# SBDBT.net
KiCad netlist of a schematic drawn in EAGLE
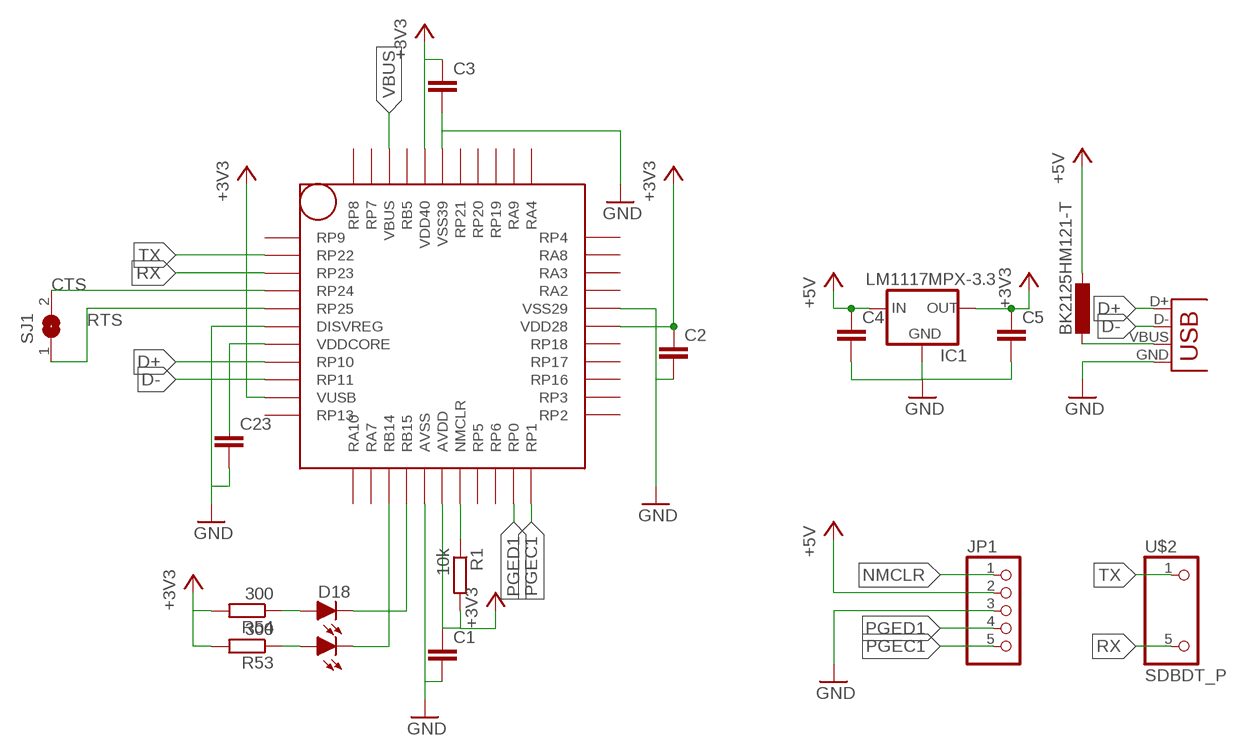
[diagram p0: schematic, sheet 1]

(export (version "E")
  (design (tool "Eeschema 10.0.6"))
  (components
    (comp (ref "BK2125HM121-T")
      (value "L-EUL2012C")
      (footprint "eagle-import:L2012C")
      (libsource (lib "eagle-import") (part "L-EUL2012C"))
    )
    (comp (ref "C1")
      (value "C-EUC0603K")
      (footprint "eagle-import:C0603K")
      (libsource (lib "eagle-import") (part "C-EUC0603K"))
    )
    (comp (ref "C2")
      (value "C-EUC0603K")
      (footprint "eagle-import:C0603K")
      (libsource (lib "eagle-import") (part "C-EUC0603K"))
    )
    (comp (ref "C3")
      (value "C-EUC0603K")
      (footprint "eagle-import:C0603K")
      (libsource (lib "eagle-import") (part "C-EUC0603K"))
    )
    (comp (ref "C4")
      (value "C-EUC0603K")
      (footprint "eagle-import:C0603K")
      (libsource (lib "eagle-import") (part "C-EUC0603K"))
    )
    (comp (ref "C5")
      (value "C-EUC0603K")
      (footprint "eagle-import:C0603K")
      (libsource (lib "eagle-import") (part "C-EUC0603K"))
    )
    (comp (ref "C23")
      (value "C-EUC0603K")
      (footprint "eagle-import:C0603K")
      (libsource (lib "eagle-import") (part "C-EUC0603K"))
    )
    (comp (ref "D18")
      (value "SEC2XX4")
      (footprint "eagle-import:LED3025")
      (libsource (lib "eagle-import") (part "SEC2XX4"))
    )
    (comp (ref "IC1")
      (value "LM1117MPX-3.3")
      (footprint "eagle-import:SOT223")
      (libsource (lib "eagle-import") (part "LM1117"))
    )
    (comp (ref "JP1")
      (value "PINHD-1X5")
      (footprint "eagle-import:1X05")
      (libsource (lib "eagle-import") (part "PINHD-1X5"))
    )
    (comp (ref "R1")
      (value "10k")
      (footprint "eagle-import:R0603")
      (libsource (lib "eagle-import") (part "R-EU_R0603"))
    )
    (comp (ref "R53")
      (value "300")
      (footprint "eagle-import:R0603")
      (libsource (lib "eagle-import") (part "R-EU_R0603"))
    )
    (comp (ref "R54")
      (value "300")
      (footprint "eagle-import:R0603")
      (libsource (lib "eagle-import") (part "R-EU_R0603"))
    )
    (comp (ref "SJ1") (value "SJ") (footprint "eagle-import:SJ") (libsource (lib "eagle-import") (part "SJ")))
    (comp (ref "U$1")
      (value "PIC24FJ64GB004")
      (footprint "eagle-import:SQFP-S-10X10-44")
      (libsource (lib "eagle-import") (part "PIC24FJ64GB004"))
    )
    (comp (ref "U$2")
      (value "SDBDT_P")
      (footprint "eagle-import:SDBDT_P")
      (libsource (lib "eagle-import") (part "SDBDT_P"))
    )
    (comp (ref "X2")
      (value "USB_")
      (footprint "eagle-import:USB-A-S-SILK-FEMALE")
      (libsource (lib "eagle-import") (part "USB_"))
    )
  )
  (nets
    (net (code "1") (name "+3V3") (class "Default")
      (node (ref "C1") (pin "1") (pinfunction "1_1") (pintype "passive"))
      (node (ref "C2") (pin "1") (pinfunction "1_1") (pintype "passive"))
      (node (ref "C3") (pin "1") (pinfunction "1_1") (pintype "passive"))
      (node (ref "C5") (pin "1") (pinfunction "1_1") (pintype "passive"))
      (node (ref "IC1") (pin "2") (pinfunction "OUT1_2") (pintype "passive"))
      (node (ref "IC1") (pin "4") (pinfunction "OUT_4") (pintype "passive"))
      (node (ref "R1") (pin "2") (pinfunction "2_2") (pintype "passive"))
      (node (ref "R53") (pin "2") (pinfunction "2_2") (pintype "passive"))
      (node (ref "R54") (pin "2") (pinfunction "2_2") (pintype "passive"))
      (node (ref "U$1") (pin "AVDD") (pinfunction "AVDD_AVDD") (pintype "bidirectional"))
      (node (ref "U$1") (pin "VDD28") (pinfunction "VDD28_VDD28") (pintype "bidirectional"))
      (node (ref "U$1") (pin "VDD40") (pinfunction "VDD40_VDD40") (pintype "bidirectional"))
      (node (ref "U$1") (pin "VUSB") (pinfunction "VUSB_VUSB") (pintype "bidirectional"))
    )
    (net (code "2") (name "+5V") (class "Default")
      (node (ref "BK2125HM121-T") (pin "1") (pinfunction "1_1") (pintype "passive"))
      (node (ref "C4") (pin "1") (pinfunction "1_1") (pintype "passive"))
      (node (ref "IC1") (pin "3") (pinfunction "IN_3") (pintype "input"))
      (node (ref "JP1") (pin "2") (pinfunction "2_2") (pintype "passive"))
    )
    (net (code "3") (name "/CTS") (class "Default")
      (node (ref "SJ1") (pin "2") (pinfunction "2_2") (pintype "passive"))
      (node (ref "U$1") (pin "RP24") (pinfunction "RP24_RP24") (pintype "bidirectional"))
    )
    (net (code "4") (name "/RTS") (class "Default")
      (node (ref "SJ1") (pin "1") (pinfunction "1_1") (pintype "passive"))
      (node (ref "U$1") (pin "RP25") (pinfunction "RP25_RP25") (pintype "bidirectional"))
    )
    (net (code "5") (name "D+") (class "Default")
      (node (ref "U$1") (pin "RP10") (pinfunction "RP10_RP10") (pintype "bidirectional"))
      (node (ref "X2") (pin "D+") (pinfunction "D+_D+") (pintype "bidirectional"))
    )
    (net (code "6") (name "D-") (class "Default")
      (node (ref "U$1") (pin "RP11") (pinfunction "RP11_RP11") (pintype "bidirectional"))
      (node (ref "X2") (pin "D-") (pinfunction "D-_D-") (pintype "bidirectional"))
    )
    (net (code "7") (name "GND") (class "Default")
      (node (ref "C1") (pin "2") (pinfunction "2_2") (pintype "passive"))
      (node (ref "C2") (pin "2") (pinfunction "2_2") (pintype "passive"))
      (node (ref "C23") (pin "2") (pinfunction "2_2") (pintype "passive"))
      (node (ref "C3") (pin "2") (pinfunction "2_2") (pintype "passive"))
      (node (ref "C4") (pin "2") (pinfunction "2_2") (pintype "passive"))
      (node (ref "C5") (pin "2") (pinfunction "2_2") (pintype "passive"))
      (node (ref "IC1") (pin "1") (pinfunction "GND_1") (pintype "input"))
      (node (ref "JP1") (pin "3") (pinfunction "3_3") (pintype "passive"))
      (node (ref "U$1") (pin "AVSS") (pinfunction "AVSS_AVSS") (pintype "bidirectional"))
      (node (ref "U$1") (pin "DISVREG") (pinfunction "DISVREG_DISVREG") (pintype "bidirectional"))
      (node (ref "U$1") (pin "VSS29") (pinfunction "VSS29_VSS29") (pintype "bidirectional"))
      (node (ref "U$1") (pin "VSS39") (pinfunction "VSS39_VSS39") (pintype "bidirectional"))
      (node (ref "X2") (pin "GND") (pinfunction "GND_GND") (pintype "bidirectional"))
    )
    (net (code "8") (name "NMCLR") (class "Default")
      (node (ref "JP1") (pin "1") (pinfunction "1_1") (pintype "passive"))
      (node (ref "R1") (pin "1") (pinfunction "1_1") (pintype "passive"))
      (node (ref "U$1") (pin "NMCLR") (pinfunction "NMCLR_NMCLR") (pintype "bidirectional"))
    )
    (net (code "9") (name "Net-(C23-Pad1)") (class "Default")
      (node (ref "C23") (pin "1") (pinfunction "1_1") (pintype "passive"))
      (node (ref "U$1") (pin "VDDCORE") (pinfunction "VDDCORE_VDDCORE") (pintype "bidirectional"))
    )
    (net (code "10") (name "Net-(D18-A0)") (class "Default")
      (node (ref "D18") (pin "4") (pinfunction "A0_4") (pintype "passive"))
      (node (ref "R54") (pin "1") (pinfunction "1_1") (pintype "passive"))
    )
    (net (code "11") (name "Net-(D18-A1)") (class "Default")
      (node (ref "D18") (pin "3") (pinfunction "A1_3") (pintype "passive"))
      (node (ref "R53") (pin "1") (pinfunction "1_1") (pintype "passive"))
    )
    (net (code "12") (name "Net-(D18-C0)") (class "Default")
      (node (ref "D18") (pin "1") (pinfunction "C0_1") (pintype "passive"))
      (node (ref "U$1") (pin "RB15") (pinfunction "RB15_RB15") (pintype "bidirectional"))
    )
    (net (code "13") (name "Net-(D18-C1)") (class "Default")
      (node (ref "D18") (pin "2") (pinfunction "C1_2") (pintype "passive"))
      (node (ref "U$1") (pin "RB14") (pinfunction "RB14_RB14") (pintype "bidirectional"))
    )
    (net (code "14") (name "PGEC1") (class "Default")
      (node (ref "JP1") (pin "5") (pinfunction "5_5") (pintype "passive"))
      (node (ref "U$1") (pin "RP1") (pinfunction "RP1_RP1") (pintype "bidirectional"))
    )
    (net (code "15") (name "PGED1") (class "Default")
      (node (ref "JP1") (pin "4") (pinfunction "4_4") (pintype "passive"))
      (node (ref "U$1") (pin "RP0") (pinfunction "RP0_RP0") (pintype "bidirectional"))
    )
    (net (code "16") (name "RX") (class "Default")
      (node (ref "U$1") (pin "RP23") (pinfunction "RP23_RP23") (pintype "bidirectional"))
      (node (ref "U$2") (pin "5") (pinfunction "5_5") (pintype "passive"))
    )
    (net (code "17") (name "TX") (class "Default")
      (node (ref "U$1") (pin "RP22") (pinfunction "RP22_RP22") (pintype "bidirectional"))
      (node (ref "U$2") (pin "1") (pinfunction "1_1") (pintype "passive"))
    )
    (net (code "18") (name "VBUS") (class "Default")
      (node (ref "BK2125HM121-T") (pin "2") (pinfunction "2_2") (pintype "passive"))
      (node (ref "U$1") (pin "VBUS") (pinfunction "VBUS_VBUS") (pintype "bidirectional"))
      (node (ref "X2") (pin "VBUS") (pinfunction "VBUS_VBUS") (pintype "bidirectional"))
    )
    (net (code "19") (name "unconnected-(U$1-PadRA2)") (class "Default")
      (node (ref "U$1") (pin "RA2") (pinfunction "RA2_RA2") (pintype "bidirectional"))
    )
    (net (code "20") (name "unconnected-(U$1-PadRA3)") (class "Default")
      (node (ref "U$1") (pin "RA3") (pinfunction "RA3_RA3") (pintype "bidirectional"))
    )
    (net (code "21") (name "unconnected-(U$1-PadRA4)") (class "Default")
      (node (ref "U$1") (pin "RA4") (pinfunction "RA4_RA4") (pintype "bidirectional"))
    )
    (net (code "22") (name "unconnected-(U$1-PadRA7)") (class "Default")
      (node (ref "U$1") (pin "RA7") (pinfunction "RA7_RA7") (pintype "bidirectional"))
    )
    (net (code "23") (name "unconnected-(U$1-PadRA8)") (class "Default")
      (node (ref "U$1") (pin "RA8") (pinfunction "RA8_RA8") (pintype "bidirectional"))
    )
    (net (code "24") (name "unconnected-(U$1-PadRA9)") (class "Default")
      (node (ref "U$1") (pin "RA9") (pinfunction "RA9_RA9") (pintype "bidirectional"))
    )
    (net (code "25") (name "unconnected-(U$1-PadRA10)") (class "Default")
      (node (ref "U$1") (pin "RA10") (pinfunction "RA10_RA10") (pintype "bidirectional"))
    )
    (net (code "26") (name "unconnected-(U$1-PadRB5)") (class "Default")
      (node (ref "U$1") (pin "RB5") (pinfunction "RB5_RB5") (pintype "bidirectional"))
    )
    (net (code "27") (name "unconnected-(U$1-PadRP2)") (class "Default")
      (node (ref "U$1") (pin "RP2") (pinfunction "RP2_RP2") (pintype "bidirectional"))
    )
    (net (code "28") (name "unconnected-(U$1-PadRP3)") (class "Default")
      (node (ref "U$1") (pin "RP3") (pinfunction "RP3_RP3") (pintype "bidirectional"))
    )
    (net (code "29") (name "unconnected-(U$1-PadRP4)") (class "Default")
      (node (ref "U$1") (pin "RP4") (pinfunction "RP4_RP4") (pintype "bidirectional"))
    )
    (net (code "30") (name "unconnected-(U$1-PadRP5)") (class "Default")
      (node (ref "U$1") (pin "RP5") (pinfunction "RP5_RP5") (pintype "bidirectional"))
    )
    (net (code "31") (name "unconnected-(U$1-PadRP6)") (class "Default")
      (node (ref "U$1") (pin "RP6") (pinfunction "RP6_RP6") (pintype "bidirectional"))
    )
    (net (code "32") (name "unconnected-(U$1-PadRP7)") (class "Default")
      (node (ref "U$1") (pin "RP7") (pinfunction "RP7_RP7") (pintype "bidirectional"))
    )
    (net (code "33") (name "unconnected-(U$1-PadRP8)") (class "Default")
      (node (ref "U$1") (pin "RP8") (pinfunction "RP8_RP8") (pintype "bidirectional"))
    )
    (net (code "34") (name "unconnected-(U$1-PadRP9)") (class "Default")
      (node (ref "U$1") (pin "RP9") (pinfunction "RP9_RP9") (pintype "bidirectional"))
    )
    (net (code "35") (name "unconnected-(U$1-PadRP13)") (class "Default")
      (node (ref "U$1") (pin "RP13") (pinfunction "RP13_RP13") (pintype "bidirectional"))
    )
    (net (code "36") (name "unconnected-(U$1-PadRP16)") (class "Default")
      (node (ref "U$1") (pin "RP16") (pinfunction "RP16_RP16") (pintype "bidirectional"))
    )
    (net (code "37") (name "unconnected-(U$1-PadRP17)") (class "Default")
      (node (ref "U$1") (pin "RP17") (pinfunction "RP17_RP17") (pintype "bidirectional"))
    )
    (net (code "38") (name "unconnected-(U$1-PadRP18)") (class "Default")
      (node (ref "U$1") (pin "RP18") (pinfunction "RP18_RP18") (pintype "bidirectional"))
    )
    (net (code "39") (name "unconnected-(U$1-PadRP19)") (class "Default")
      (node (ref "U$1") (pin "RP19") (pinfunction "RP19_RP19") (pintype "bidirectional"))
    )
    (net (code "40") (name "unconnected-(U$1-PadRP20)") (class "Default")
      (node (ref "U$1") (pin "RP20") (pinfunction "RP20_RP20") (pintype "bidirectional"))
    )
    (net (code "41") (name "unconnected-(U$1-PadRP21)") (class "Default")
      (node (ref "U$1") (pin "RP21") (pinfunction "RP21_RP21") (pintype "bidirectional"))
    )
  )
)
